# PIC32_breakout.net
KiCad netlist of a schematic drawn in EAGLE
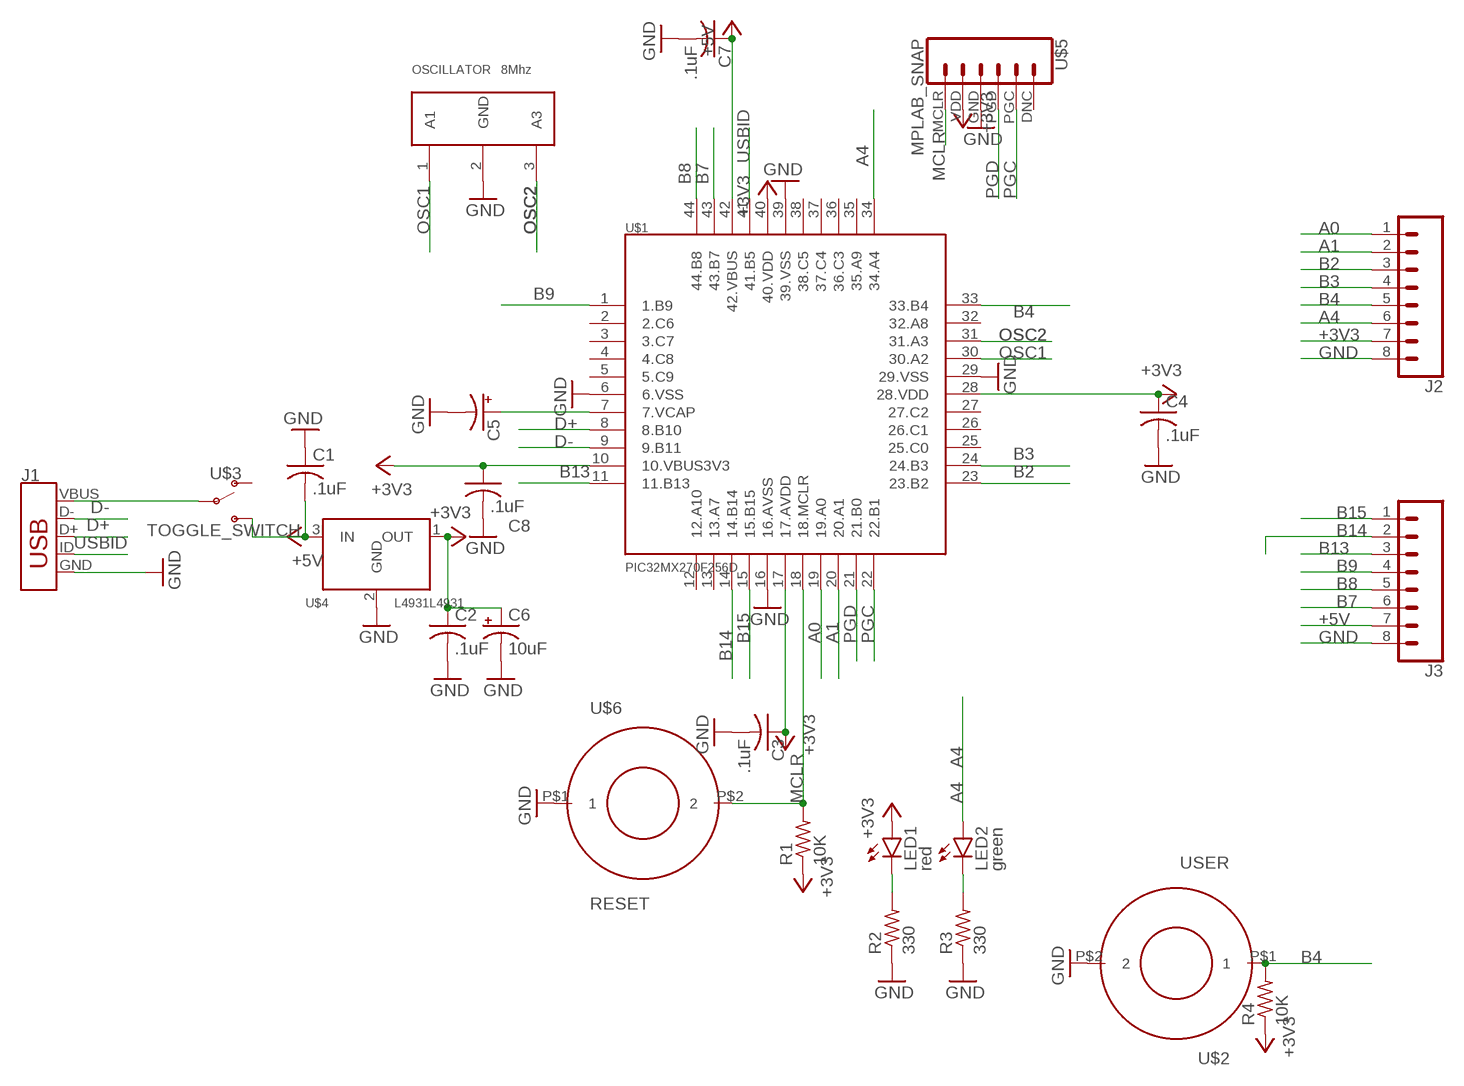
[diagram p0: schematic, sheet 1]

(export (version "E")
  (design (tool "Eeschema 10.0.6"))
  (components
    (comp (ref "C1")
      (value ".1uF")
      (footprint "eagle-import:C025-025X050")
      (libsource (lib "eagle-import") (part "C-US025-025X050"))
    )
    (comp (ref "C2")
      (value ".1uF")
      (footprint "eagle-import:C025-025X050")
      (libsource (lib "eagle-import") (part "C-US025-025X050"))
    )
    (comp (ref "C3")
      (value ".1uF")
      (footprint "eagle-import:C025-025X050")
      (libsource (lib "eagle-import") (part "C-US025-025X050"))
    )
    (comp (ref "C4")
      (value ".1uF")
      (footprint "eagle-import:C025-025X050")
      (libsource (lib "eagle-import") (part "C-US025-025X050"))
    )
    (comp (ref "C5")
      (value "CPOL-USB45181B")
      (footprint "eagle-import:B45181B")
      (libsource (lib "eagle-import") (part "CPOL-USB45181B"))
    )
    (comp (ref "C6")
      (value "10uF")
      (footprint "eagle-import:B45181B")
      (libsource (lib "eagle-import") (part "CPOL-USB45181B"))
    )
    (comp (ref "C7")
      (value ".1uF")
      (footprint "eagle-import:C025-025X050")
      (libsource (lib "eagle-import") (part "C-US025-025X050"))
    )
    (comp (ref "C8")
      (value ".1uF")
      (footprint "eagle-import:C025-025X050")
      (libsource (lib "eagle-import") (part "C-US025-025X050"))
    )
    (comp (ref "J1")
      (value "USB_MICRO-B")
      (footprint "eagle-import:AMPHENOL609-4618-1-ND")
      (libsource (lib "eagle-import") (part "USB_MICRO-B"))
    )
    (comp (ref "J2")
      (value "CONN_08\"")
      (footprint "eagle-import:1X08")
      (libsource (lib "eagle-import") (part "CONN_08{dblquote}"))
    )
    (comp (ref "J3")
      (value "CONN_08\"")
      (footprint "eagle-import:1X08")
      (libsource (lib "eagle-import") (part "CONN_08{dblquote}"))
    )
    (comp (ref "LED1")
      (value "red")
      (footprint "eagle-import:LED3MM")
      (libsource (lib "eagle-import") (part "LED3MM"))
    )
    (comp (ref "LED2")
      (value "green")
      (footprint "eagle-import:LED3MM")
      (libsource (lib "eagle-import") (part "LED3MM"))
    )
    (comp (ref "OSCILLATOR")
      (value "8Mhz")
      (footprint "eagle-import:1X03")
      (libsource (lib "eagle-import") (part "RESONATOR"))
    )
    (comp (ref "R1")
      (value "10K")
      (footprint "eagle-import:0207_10")
      (libsource (lib "eagle-import") (part "R-US_0207/10"))
    )
    (comp (ref "R2")
      (value "330")
      (footprint "eagle-import:0207_10")
      (libsource (lib "eagle-import") (part "R-US_0207/10"))
    )
    (comp (ref "R3")
      (value "330")
      (footprint "eagle-import:0207_10")
      (libsource (lib "eagle-import") (part "R-US_0207/10"))
    )
    (comp (ref "R4")
      (value "10K")
      (footprint "eagle-import:0207_10")
      (libsource (lib "eagle-import") (part "R-US_0207/10"))
    )
    (comp (ref "U$1")
      (value "PIC32MX270F256D")
      (footprint "eagle-import:TQFP44")
      (libsource (lib "eagle-import") (part "PIC32MX270F256D"))
    )
    (comp (ref "U$2")
      (value "USER")
      (footprint "eagle-import:BTN_2")
      (libsource (lib "eagle-import") (part "SWITCH_BTN_NO"))
    )
    (comp (ref "U$3")
      (value "TOGGLE_SWITCH")
      (footprint "eagle-import:TOGGLE")
      (libsource (lib "eagle-import") (part "TOGGLE_SWITCH"))
    )
    (comp (ref "U$4")
      (value "L4931L4931")
      (footprint "eagle-import:TO92")
      (libsource (lib "eagle-import") (part "L4931L4931"))
    )
    (comp (ref "U$5")
      (value "MPLAB_SNAP")
      (footprint "eagle-import:1X06")
      (libsource (lib "eagle-import") (part "MPLAB_SNAP"))
    )
    (comp (ref "U$6")
      (value "RESET")
      (footprint "eagle-import:BTN_2")
      (libsource (lib "eagle-import") (part "SWITCH_BTN_NO"))
    )
  )
  (nets
    (net (code "1") (name "+3V3") (class "Default")
      (node (ref "C2") (pin "1") (pinfunction "1_1") (pintype "passive"))
      (node (ref "C3") (pin "1") (pinfunction "1_1") (pintype "passive"))
      (node (ref "C4") (pin "1") (pinfunction "1_1") (pintype "passive"))
      (node (ref "C6") (pin "+") (pinfunction "+_+") (pintype "passive"))
      (node (ref "C8") (pin "1") (pinfunction "1_1") (pintype "passive"))
      (node (ref "J2") (pin "7") (pinfunction "7_7") (pintype "passive"))
      (node (ref "LED1") (pin "A") (pinfunction "A_A") (pintype "passive"))
      (node (ref "R1") (pin "1") (pinfunction "1_1") (pintype "passive"))
      (node (ref "R4") (pin "1") (pinfunction "1_1") (pintype "passive"))
      (node (ref "U$1") (pin "10") (pinfunction "10.VBUS3V3_10") (pintype "bidirectional"))
      (node (ref "U$1") (pin "17") (pinfunction "17.AVDD_17") (pintype "bidirectional"))
      (node (ref "U$1") (pin "28") (pinfunction "28.VDD_28") (pintype "bidirectional"))
      (node (ref "U$1") (pin "40") (pinfunction "40.VDD_40") (pintype "bidirectional"))
      (node (ref "U$4") (pin "1") (pinfunction "OUT_1") (pintype "bidirectional"))
      (node (ref "U$5") (pin "VDD") (pinfunction "VDD_VDD") (pintype "passive"))
    )
    (net (code "2") (name "+5V") (class "Default")
      (node (ref "C1") (pin "2") (pinfunction "2_2") (pintype "passive"))
      (node (ref "C7") (pin "1") (pinfunction "1_1") (pintype "passive"))
      (node (ref "J3") (pin "7") (pinfunction "7_7") (pintype "passive"))
      (node (ref "U$1") (pin "42") (pinfunction "42.VBUS_42") (pintype "bidirectional"))
      (node (ref "U$3") (pin "P$3") (pinfunction "OUT2_P$3") (pintype "passive"))
      (node (ref "U$4") (pin "3") (pinfunction "IN_3") (pintype "bidirectional"))
    )
    (net (code "3") (name "/A0") (class "Default")
      (node (ref "J2") (pin "1") (pinfunction "1_1") (pintype "passive"))
      (node (ref "U$1") (pin "19") (pinfunction "19.A0_19") (pintype "bidirectional"))
    )
    (net (code "4") (name "/A1") (class "Default")
      (node (ref "J2") (pin "2") (pinfunction "2_2") (pintype "passive"))
      (node (ref "U$1") (pin "20") (pinfunction "20.A1_20") (pintype "bidirectional"))
    )
    (net (code "5") (name "/A4") (class "Default")
      (node (ref "J2") (pin "6") (pinfunction "6_6") (pintype "passive"))
      (node (ref "LED2") (pin "A") (pinfunction "A_A") (pintype "passive"))
      (node (ref "U$1") (pin "34") (pinfunction "34.A4_34") (pintype "bidirectional"))
    )
    (net (code "6") (name "/B2") (class "Default")
      (node (ref "J2") (pin "3") (pinfunction "3_3") (pintype "passive"))
      (node (ref "U$1") (pin "23") (pinfunction "23.B2_23") (pintype "bidirectional"))
    )
    (net (code "7") (name "/B3") (class "Default")
      (node (ref "J2") (pin "4") (pinfunction "4_4") (pintype "passive"))
      (node (ref "U$1") (pin "24") (pinfunction "24.B3_24") (pintype "bidirectional"))
    )
    (net (code "8") (name "/B4") (class "Default")
      (node (ref "J2") (pin "5") (pinfunction "5_5") (pintype "passive"))
      (node (ref "R4") (pin "2") (pinfunction "2_2") (pintype "passive"))
      (node (ref "U$1") (pin "33") (pinfunction "33.B4_33") (pintype "bidirectional"))
      (node (ref "U$2") (pin "P$1") (pinfunction "1_P$1") (pintype "bidirectional"))
    )
    (net (code "9") (name "/B7") (class "Default")
      (node (ref "J3") (pin "6") (pinfunction "6_6") (pintype "passive"))
      (node (ref "U$1") (pin "43") (pinfunction "43.B7_43") (pintype "bidirectional"))
    )
    (net (code "10") (name "/B8") (class "Default")
      (node (ref "J3") (pin "5") (pinfunction "5_5") (pintype "passive"))
      (node (ref "U$1") (pin "44") (pinfunction "44.B8_44") (pintype "bidirectional"))
    )
    (net (code "11") (name "/B9") (class "Default")
      (node (ref "J3") (pin "4") (pinfunction "4_4") (pintype "passive"))
      (node (ref "U$1") (pin "1") (pinfunction "1.B9_1") (pintype "bidirectional"))
    )
    (net (code "12") (name "/B13") (class "Default")
      (node (ref "J3") (pin "3") (pinfunction "3_3") (pintype "passive"))
      (node (ref "U$1") (pin "11") (pinfunction "11.B13_11") (pintype "bidirectional"))
    )
    (net (code "13") (name "/B14") (class "Default")
      (node (ref "J3") (pin "2") (pinfunction "2_2") (pintype "passive"))
      (node (ref "U$1") (pin "14") (pinfunction "14.B14_14") (pintype "bidirectional"))
    )
    (net (code "14") (name "/B15") (class "Default")
      (node (ref "J3") (pin "1") (pinfunction "1_1") (pintype "passive"))
      (node (ref "U$1") (pin "15") (pinfunction "15.B15_15") (pintype "bidirectional"))
    )
    (net (code "15") (name "/D+") (class "Default")
      (node (ref "J1") (pin "D+") (pinfunction "D+_D+") (pintype "bidirectional"))
      (node (ref "U$1") (pin "8") (pinfunction "8.B10_8") (pintype "bidirectional"))
    )
    (net (code "16") (name "/D-") (class "Default")
      (node (ref "J1") (pin "D-") (pinfunction "D-_D-") (pintype "bidirectional"))
      (node (ref "U$1") (pin "9") (pinfunction "9.B11_9") (pintype "bidirectional"))
    )
    (net (code "17") (name "/MCLR") (class "Default")
      (node (ref "R1") (pin "2") (pinfunction "2_2") (pintype "passive"))
      (node (ref "U$1") (pin "18") (pinfunction "18.MCLR_18") (pintype "bidirectional"))
      (node (ref "U$5") (pin "MCLR") (pinfunction "MCLR_MCLR") (pintype "passive"))
      (node (ref "U$6") (pin "P$2") (pinfunction "2_P$2") (pintype "bidirectional"))
    )
    (net (code "18") (name "/OSC1") (class "Default")
      (node (ref "OSCILLATOR") (pin "1") (pinfunction "A1_1") (pintype "bidirectional"))
      (node (ref "U$1") (pin "30") (pinfunction "30.A2_30") (pintype "bidirectional"))
    )
    (net (code "19") (name "/OSC2") (class "Default")
      (node (ref "OSCILLATOR") (pin "3") (pinfunction "A3_3") (pintype "bidirectional"))
      (node (ref "U$1") (pin "31") (pinfunction "31.A3_31") (pintype "bidirectional"))
    )
    (net (code "20") (name "/PGC") (class "Default")
      (node (ref "U$1") (pin "22") (pinfunction "22.B1_22") (pintype "bidirectional"))
      (node (ref "U$5") (pin "PGC") (pinfunction "PGC_PGC") (pintype "passive"))
    )
    (net (code "21") (name "/PGD") (class "Default")
      (node (ref "U$1") (pin "21") (pinfunction "21.B0_21") (pintype "bidirectional"))
      (node (ref "U$5") (pin "PGD") (pinfunction "PGD_PGD") (pintype "passive"))
    )
    (net (code "22") (name "/USBID") (class "Default")
      (node (ref "J1") (pin "ID") (pinfunction "ID_ID") (pintype "bidirectional"))
      (node (ref "U$1") (pin "41") (pinfunction "41.B5_41") (pintype "bidirectional"))
    )
    (net (code "23") (name "GND") (class "Default")
      (node (ref "C1") (pin "1") (pinfunction "1_1") (pintype "passive"))
      (node (ref "C2") (pin "2") (pinfunction "2_2") (pintype "passive"))
      (node (ref "C3") (pin "2") (pinfunction "2_2") (pintype "passive"))
      (node (ref "C4") (pin "2") (pinfunction "2_2") (pintype "passive"))
      (node (ref "C5") (pin "-") (pinfunction "-_-") (pintype "passive"))
      (node (ref "C6") (pin "-") (pinfunction "-_-") (pintype "passive"))
      (node (ref "C7") (pin "2") (pinfunction "2_2") (pintype "passive"))
      (node (ref "C8") (pin "2") (pinfunction "2_2") (pintype "passive"))
      (node (ref "J1") (pin "GND") (pinfunction "GND_GND") (pintype "power_in"))
      (node (ref "J2") (pin "8") (pinfunction "8_8") (pintype "passive"))
      (node (ref "J3") (pin "8") (pinfunction "8_8") (pintype "passive"))
      (node (ref "OSCILLATOR") (pin "2") (pinfunction "GND_2") (pintype "bidirectional"))
      (node (ref "R2") (pin "1") (pinfunction "1_1") (pintype "passive"))
      (node (ref "R3") (pin "1") (pinfunction "1_1") (pintype "passive"))
      (node (ref "U$1") (pin "16") (pinfunction "16.AVSS_16") (pintype "bidirectional"))
      (node (ref "U$1") (pin "29") (pinfunction "29.VSS_29") (pintype "bidirectional"))
      (node (ref "U$1") (pin "39") (pinfunction "39.VSS_39") (pintype "bidirectional"))
      (node (ref "U$1") (pin "6") (pinfunction "6.VSS_6") (pintype "bidirectional"))
      (node (ref "U$2") (pin "P$2") (pinfunction "2_P$2") (pintype "bidirectional"))
      (node (ref "U$4") (pin "2") (pinfunction "GND_2") (pintype "bidirectional"))
      (node (ref "U$5") (pin "GND") (pinfunction "GND_GND") (pintype "passive"))
      (node (ref "U$6") (pin "P$1") (pinfunction "1_P$1") (pintype "bidirectional"))
    )
    (net (code "24") (name "Net-(LED1-C)") (class "Default")
      (node (ref "LED1") (pin "K") (pinfunction "C_K") (pintype "passive"))
      (node (ref "R2") (pin "2") (pinfunction "2_2") (pintype "passive"))
    )
    (net (code "25") (name "Net-(LED2-C)") (class "Default")
      (node (ref "LED2") (pin "K") (pinfunction "C_K") (pintype "passive"))
      (node (ref "R3") (pin "2") (pinfunction "2_2") (pintype "passive"))
    )
    (net (code "26") (name "Net-(U$1-7.VCAP)") (class "Default")
      (node (ref "C5") (pin "+") (pinfunction "+_+") (pintype "passive"))
      (node (ref "U$1") (pin "7") (pinfunction "7.VCAP_7") (pintype "bidirectional"))
    )
    (net (code "27") (name "Net-(U$3-IN)") (class "Default")
      (node (ref "J1") (pin "VBUS") (pinfunction "VBUS_VBUS") (pintype "power_in"))
      (node (ref "U$3") (pin "P$1") (pinfunction "IN_P$1") (pintype "passive"))
    )
    (net (code "28") (name "unconnected-(U$1-2.C6-Pad2)") (class "Default")
      (node (ref "U$1") (pin "2") (pinfunction "2.C6_2") (pintype "bidirectional"))
    )
    (net (code "29") (name "unconnected-(U$1-3.C7-Pad3)") (class "Default")
      (node (ref "U$1") (pin "3") (pinfunction "3.C7_3") (pintype "bidirectional"))
    )
    (net (code "30") (name "unconnected-(U$1-4.C8-Pad4)") (class "Default")
      (node (ref "U$1") (pin "4") (pinfunction "4.C8_4") (pintype "bidirectional"))
    )
    (net (code "31") (name "unconnected-(U$1-5.C9-Pad5)") (class "Default")
      (node (ref "U$1") (pin "5") (pinfunction "5.C9_5") (pintype "bidirectional"))
    )
    (net (code "32") (name "unconnected-(U$1-12.A10-Pad12)") (class "Default")
      (node (ref "U$1") (pin "12") (pinfunction "12.A10_12") (pintype "bidirectional"))
    )
    (net (code "33") (name "unconnected-(U$1-13.A7-Pad13)") (class "Default")
      (node (ref "U$1") (pin "13") (pinfunction "13.A7_13") (pintype "bidirectional"))
    )
    (net (code "34") (name "unconnected-(U$1-25.C0-Pad25)") (class "Default")
      (node (ref "U$1") (pin "25") (pinfunction "25.C0_25") (pintype "bidirectional"))
    )
    (net (code "35") (name "unconnected-(U$1-26.C1-Pad26)") (class "Default")
      (node (ref "U$1") (pin "26") (pinfunction "26.C1_26") (pintype "bidirectional"))
    )
    (net (code "36") (name "unconnected-(U$1-27.C2-Pad27)") (class "Default")
      (node (ref "U$1") (pin "27") (pinfunction "27.C2_27") (pintype "bidirectional"))
    )
    (net (code "37") (name "unconnected-(U$1-32.A8-Pad32)") (class "Default")
      (node (ref "U$1") (pin "32") (pinfunction "32.A8_32") (pintype "bidirectional"))
    )
    (net (code "38") (name "unconnected-(U$1-35.A9-Pad35)") (class "Default")
      (node (ref "U$1") (pin "35") (pinfunction "35.A9_35") (pintype "bidirectional"))
    )
    (net (code "39") (name "unconnected-(U$1-36.C3-Pad36)") (class "Default")
      (node (ref "U$1") (pin "36") (pinfunction "36.C3_36") (pintype "bidirectional"))
    )
    (net (code "40") (name "unconnected-(U$1-37.C4-Pad37)") (class "Default")
      (node (ref "U$1") (pin "37") (pinfunction "37.C4_37") (pintype "bidirectional"))
    )
    (net (code "41") (name "unconnected-(U$1-38.C5-Pad38)") (class "Default")
      (node (ref "U$1") (pin "38") (pinfunction "38.C5_38") (pintype "bidirectional"))
    )
    (net (code "42") (name "unconnected-(U$3-OUT1-PadP$2)") (class "Default")
      (node (ref "U$3") (pin "P$2") (pinfunction "OUT1_P$2") (pintype "passive"))
    )
    (net (code "43") (name "unconnected-(U$5-PadDNC)") (class "Default")
      (node (ref "U$5") (pin "DNC") (pinfunction "DNC_DNC") (pintype "passive"))
    )
  )
)
